# RH034_2.net
KiCad netlist of a schematic drawn in EAGLE
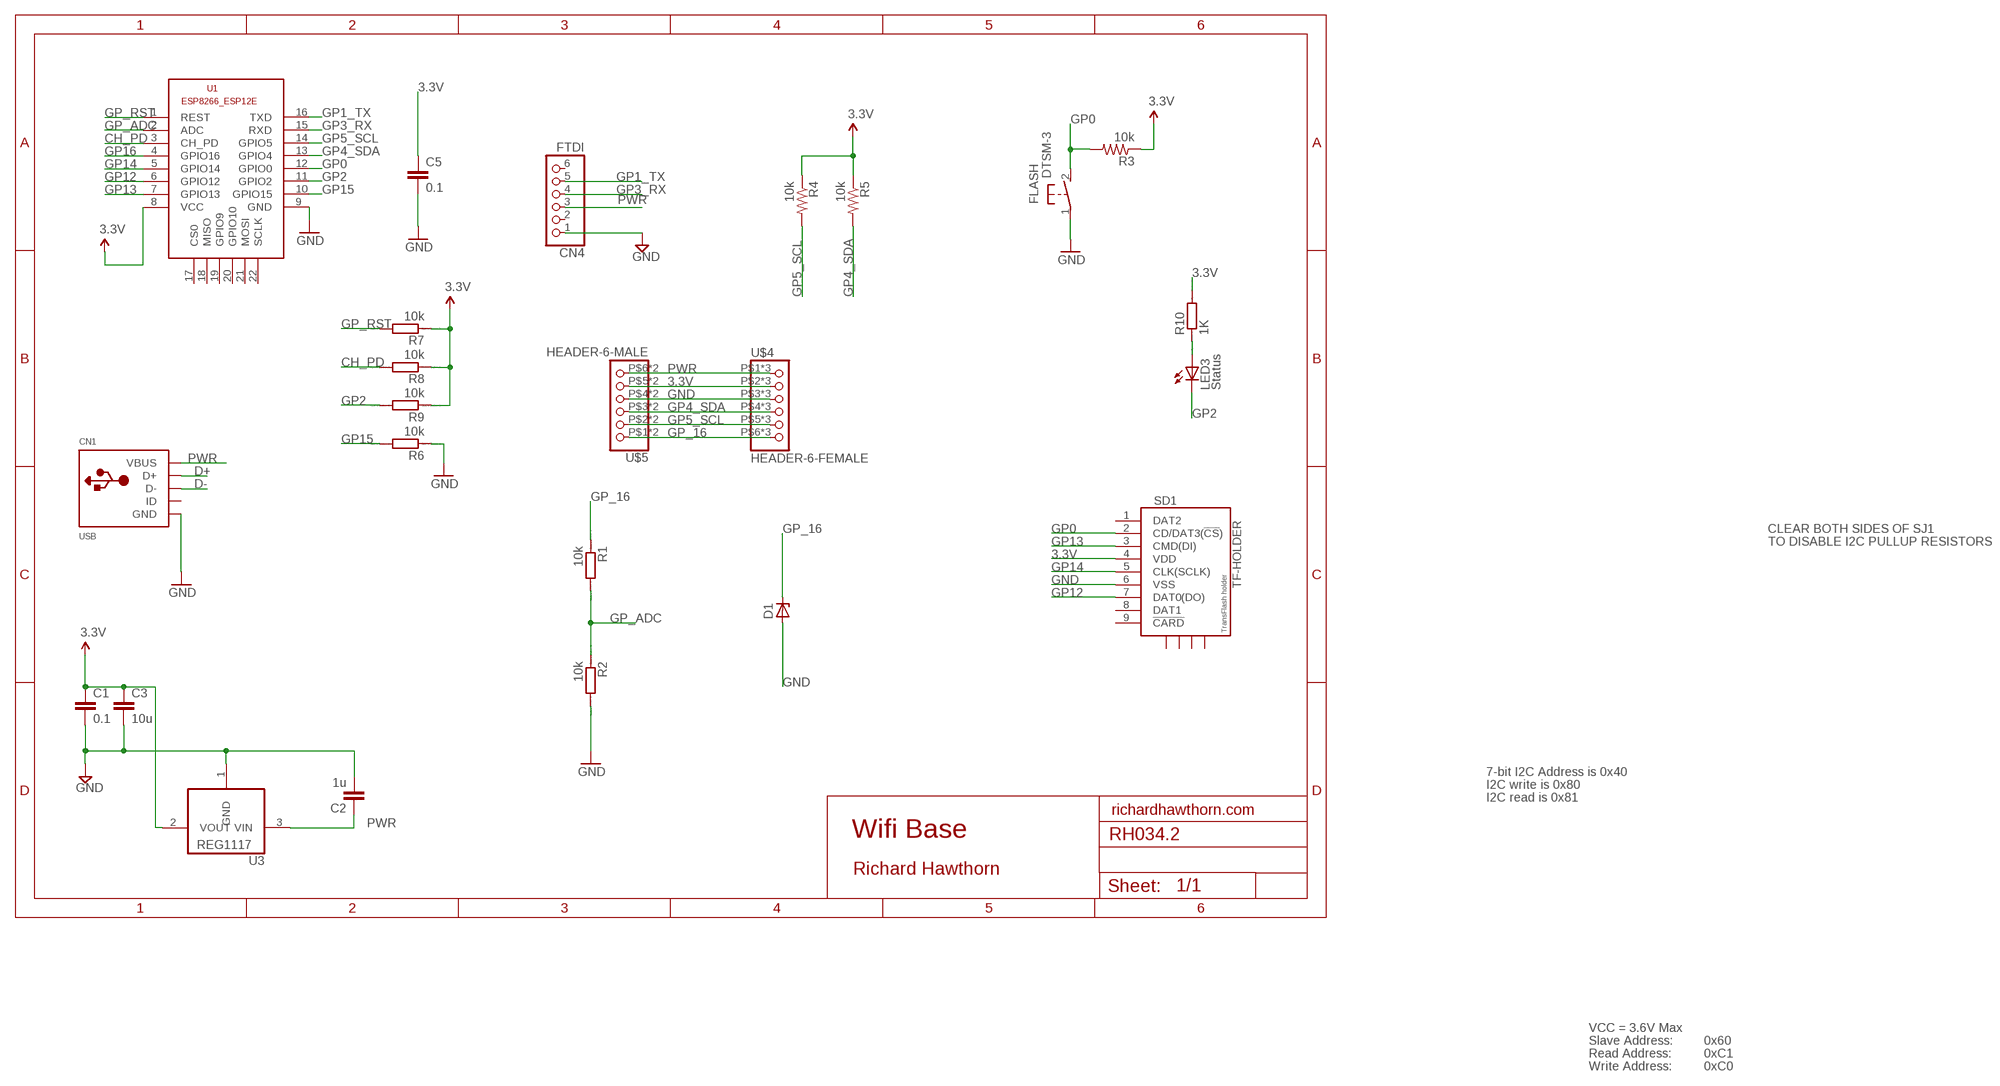
[diagram p0: schematic, sheet 1]

(export (version "E")
  (design (tool "Eeschema 10.0.6"))
  (components
    (comp (ref "C1")
      (value "0.1")
      (footprint "eagle-import:0603-CAP")
      (libsource (lib "eagle-import") (part "CAP0603-CAP"))
    )
    (comp (ref "C2")
      (value "1u")
      (footprint "eagle-import:0603-CAP")
      (libsource (lib "eagle-import") (part "CAP0603-CAP"))
    )
    (comp (ref "C3")
      (value "10u")
      (footprint "eagle-import:0805-CAP")
      (libsource (lib "eagle-import") (part "CAP0805-CAP"))
    )
    (comp (ref "C5")
      (value "0.1")
      (footprint "eagle-import:0603-CAP")
      (libsource (lib "eagle-import") (part "CAP0603-CAP"))
    )
    (comp (ref "CN1")
      (value "USB")
      (footprint "eagle-import:USB-MINIB")
      (libsource (lib "eagle-import") (part "USBMINIB"))
    )
    (comp (ref "CN4")
      (value "FTDI")
      (footprint "eagle-import:1X06")
      (libsource (lib "eagle-import") (part "PINHD-1X6"))
    )
    (comp (ref "D1")
      (value "ZENER-DIODESOT23")
      (footprint "eagle-import:SOT23")
      (libsource (lib "eagle-import") (part "ZENER-DIODESOT23"))
    )
    (comp (ref "FLASH")
      (value "DTSM-3")
      (footprint "eagle-import:DTSM-3")
      (libsource (lib "eagle-import") (part "DTSM-3"))
    )
    (comp (ref "LED3")
      (value "Status")
      (footprint "eagle-import:CHIPLED_0805")
      (libsource (lib "eagle-import") (part "LEDCHIPLED_0805"))
    )
    (comp (ref "R1")
      (value "10k")
      (footprint "eagle-import:R0603")
      (libsource (lib "eagle-import") (part "R-EU_R0603"))
    )
    (comp (ref "R2")
      (value "10k")
      (footprint "eagle-import:R0603")
      (libsource (lib "eagle-import") (part "R-EU_R0603"))
    )
    (comp (ref "R3")
      (value "10k")
      (footprint "eagle-import:0805")
      (libsource (lib "eagle-import") (part "RESISTOR0805-RES"))
    )
    (comp (ref "R4")
      (value "10k")
      (footprint "eagle-import:0805")
      (libsource (lib "eagle-import") (part "RESISTOR0805-RES"))
    )
    (comp (ref "R5")
      (value "10k")
      (footprint "eagle-import:0805")
      (libsource (lib "eagle-import") (part "RESISTOR0805-RES"))
    )
    (comp (ref "R6")
      (value "10k")
      (footprint "eagle-import:R0603")
      (libsource (lib "eagle-import") (part "R-EU_R0603"))
    )
    (comp (ref "R7")
      (value "10k")
      (footprint "eagle-import:R0603")
      (libsource (lib "eagle-import") (part "R-EU_R0603"))
    )
    (comp (ref "R8")
      (value "10k")
      (footprint "eagle-import:R0603")
      (libsource (lib "eagle-import") (part "R-EU_R0603"))
    )
    (comp (ref "R9")
      (value "10k")
      (footprint "eagle-import:R0603")
      (libsource (lib "eagle-import") (part "R-EU_R0603"))
    )
    (comp (ref "R10")
      (value "1K")
      (footprint "eagle-import:R0603")
      (libsource (lib "eagle-import") (part "R-EU_R0603"))
    )
    (comp (ref "SD1")
      (value "TF-HOLDER")
      (footprint "eagle-import:TF-PULL")
      (libsource (lib "eagle-import") (part "TF-HOLDER"))
    )
    (comp (ref "U$4")
      (value "HEADER-6-FEMALE")
      (footprint "eagle-import:2MMHEADER6")
      (libsource (lib "eagle-import") (part "HEADER-6-FEMALE"))
    )
    (comp (ref "U$5")
      (value "HEADER-6-MALE")
      (footprint "eagle-import:2MMHEADERPIN6")
      (libsource (lib "eagle-import") (part "HEADER-6-MALE"))
    )
    (comp (ref "U1")
      (value "ESP8266-12EESP8266-ESP12E")
      (footprint "eagle-import:ESP8266-ESP12E")
      (libsource (lib "eagle-import") (part "ESP8266-12EESP8266-ESP12E"))
    )
    (comp (ref "U3")
      (value "REG1117")
      (footprint "eagle-import:SOT223")
      (libsource (lib "eagle-import") (part "REG1117"))
    )
  )
  (nets
    (net (code "1") (name "/CH_PD") (class "Default")
      (node (ref "R8") (pin "2") (pinfunction "2_2") (pintype "passive"))
      (node (ref "U1") (pin "3") (pinfunction "CH_PD_3") (pintype "bidirectional"))
    )
    (net (code "2") (name "/D+") (class "Default")
      (node (ref "CN1") (pin "D+") (pinfunction "D+_D+") (pintype "bidirectional"))
    )
    (net (code "3") (name "/D-") (class "Default")
      (node (ref "CN1") (pin "D-") (pinfunction "D-_D-") (pintype "bidirectional"))
    )
    (net (code "4") (name "/GP0") (class "Default")
      (node (ref "FLASH") (pin "2") (pinfunction "2_2") (pintype "passive"))
      (node (ref "R3") (pin "2") (pinfunction "2_2") (pintype "passive"))
      (node (ref "SD1") (pin "2") (pinfunction "CD/DAT3(~{CS})_2") (pintype "bidirectional"))
      (node (ref "U1") (pin "12") (pinfunction "GPIO0_12") (pintype "bidirectional"))
    )
    (net (code "5") (name "/GP1_TX") (class "Default")
      (node (ref "CN4") (pin "5") (pinfunction "5_5") (pintype "passive"))
      (node (ref "U1") (pin "16") (pinfunction "TXD_16") (pintype "bidirectional"))
    )
    (net (code "6") (name "/GP2") (class "Default")
      (node (ref "LED3") (pin "C") (pinfunction "C_C") (pintype "passive"))
      (node (ref "R9") (pin "2") (pinfunction "2_2") (pintype "passive"))
      (node (ref "U1") (pin "11") (pinfunction "GPIO2_11") (pintype "bidirectional"))
    )
    (net (code "7") (name "/GP3_RX") (class "Default")
      (node (ref "CN4") (pin "4") (pinfunction "4_4") (pintype "passive"))
      (node (ref "U1") (pin "15") (pinfunction "RXD_15") (pintype "bidirectional"))
    )
    (net (code "8") (name "/GP4_SDA") (class "Default")
      (node (ref "R5") (pin "2") (pinfunction "2_2") (pintype "passive"))
      (node (ref "U$4") (pin "P$12") (pinfunction "4_P$12") (pintype "passive"))
      (node (ref "U$4") (pin "P$20") (pinfunction "4_P$20") (pintype "passive"))
      (node (ref "U$4") (pin "P$4") (pinfunction "4_P$4") (pintype "passive"))
      (node (ref "U$5") (pin "P$11") (pinfunction "3_P$11") (pintype "passive"))
      (node (ref "U$5") (pin "P$3") (pinfunction "3_P$3") (pintype "passive"))
      (node (ref "U1") (pin "13") (pinfunction "GPIO4_13") (pintype "bidirectional"))
    )
    (net (code "9") (name "/GP5_SCL") (class "Default")
      (node (ref "R4") (pin "2") (pinfunction "2_2") (pintype "passive"))
      (node (ref "U$4") (pin "P$13") (pinfunction "5_P$13") (pintype "passive"))
      (node (ref "U$4") (pin "P$21") (pinfunction "5_P$21") (pintype "passive"))
      (node (ref "U$4") (pin "P$5") (pinfunction "5_P$5") (pintype "passive"))
      (node (ref "U$5") (pin "P$10") (pinfunction "2_P$10") (pintype "passive"))
      (node (ref "U$5") (pin "P$2") (pinfunction "2_P$2") (pintype "passive"))
      (node (ref "U1") (pin "14") (pinfunction "GPIO5_14") (pintype "bidirectional"))
    )
    (net (code "10") (name "/GP12") (class "Default")
      (node (ref "SD1") (pin "7") (pinfunction "DAT0(DO)_7") (pintype "bidirectional"))
      (node (ref "U1") (pin "6") (pinfunction "GPIO12_6") (pintype "bidirectional"))
    )
    (net (code "11") (name "/GP13") (class "Default")
      (node (ref "SD1") (pin "3") (pinfunction "CMD(DI)_3") (pintype "bidirectional"))
      (node (ref "U1") (pin "7") (pinfunction "GPIO13_7") (pintype "bidirectional"))
    )
    (net (code "12") (name "/GP14") (class "Default")
      (node (ref "SD1") (pin "5") (pinfunction "CLK(SCLK)_5") (pintype "input"))
      (node (ref "U1") (pin "5") (pinfunction "GPIO14_5") (pintype "bidirectional"))
    )
    (net (code "13") (name "/GP15") (class "Default")
      (node (ref "R6") (pin "2") (pinfunction "2_2") (pintype "passive"))
      (node (ref "U1") (pin "10") (pinfunction "GPIO15_10") (pintype "bidirectional"))
    )
    (net (code "14") (name "/GP16") (class "Default")
      (node (ref "U1") (pin "4") (pinfunction "GPIO16_4") (pintype "bidirectional"))
    )
    (net (code "15") (name "/GP_16") (class "Default")
      (node (ref "D1") (pin "3") (pinfunction "C_3") (pintype "passive"))
      (node (ref "R1") (pin "1") (pinfunction "1_1") (pintype "passive"))
      (node (ref "U$4") (pin "P$14") (pinfunction "6_P$14") (pintype "passive"))
      (node (ref "U$4") (pin "P$22") (pinfunction "6_P$22") (pintype "passive"))
      (node (ref "U$4") (pin "P$6") (pinfunction "6_P$6") (pintype "passive"))
      (node (ref "U$5") (pin "P$1") (pinfunction "1_P$1") (pintype "passive"))
      (node (ref "U$5") (pin "P$9") (pinfunction "1_P$9") (pintype "passive"))
    )
    (net (code "16") (name "/GP_ADC") (class "Default")
      (node (ref "R1") (pin "2") (pinfunction "2_2") (pintype "passive"))
      (node (ref "R2") (pin "1") (pinfunction "1_1") (pintype "passive"))
      (node (ref "U1") (pin "2") (pinfunction "ADC_2") (pintype "bidirectional"))
    )
    (net (code "17") (name "/GP_RST") (class "Default")
      (node (ref "R7") (pin "2") (pinfunction "2_2") (pintype "passive"))
      (node (ref "U1") (pin "1") (pinfunction "REST_1") (pintype "bidirectional"))
    )
    (net (code "18") (name "/PWR") (class "Default")
      (node (ref "C2") (pin "1") (pinfunction "1_1") (pintype "passive"))
      (node (ref "CN1") (pin "VBUS") (pinfunction "VBUS_VBUS") (pintype "power_in"))
      (node (ref "CN4") (pin "3") (pinfunction "3_3") (pintype "passive"))
      (node (ref "U$4") (pin "P$1") (pinfunction "1_P$1") (pintype "passive"))
      (node (ref "U$4") (pin "P$17") (pinfunction "1_P$17") (pintype "passive"))
      (node (ref "U$4") (pin "P$9") (pinfunction "1_P$9") (pintype "passive"))
      (node (ref "U$5") (pin "P$14") (pinfunction "6_P$14") (pintype "passive"))
      (node (ref "U$5") (pin "P$6") (pinfunction "6_P$6") (pintype "passive"))
      (node (ref "U3") (pin "3") (pinfunction "VIN_3") (pintype "input"))
    )
    (net (code "19") (name "3.3V") (class "Default")
      (node (ref "C1") (pin "1") (pinfunction "1_1") (pintype "passive"))
      (node (ref "C3") (pin "1") (pinfunction "1_1") (pintype "passive"))
      (node (ref "C5") (pin "1") (pinfunction "1_1") (pintype "passive"))
      (node (ref "R10") (pin "2") (pinfunction "2_2") (pintype "passive"))
      (node (ref "R3") (pin "1") (pinfunction "1_1") (pintype "passive"))
      (node (ref "R4") (pin "1") (pinfunction "1_1") (pintype "passive"))
      (node (ref "R5") (pin "1") (pinfunction "1_1") (pintype "passive"))
      (node (ref "R7") (pin "1") (pinfunction "1_1") (pintype "passive"))
      (node (ref "R8") (pin "1") (pinfunction "1_1") (pintype "passive"))
      (node (ref "R9") (pin "1") (pinfunction "1_1") (pintype "passive"))
      (node (ref "SD1") (pin "4") (pinfunction "VDD_4") (pintype "power_in"))
      (node (ref "U$4") (pin "P$10") (pinfunction "2_P$10") (pintype "passive"))
      (node (ref "U$4") (pin "P$18") (pinfunction "2_P$18") (pintype "passive"))
      (node (ref "U$4") (pin "P$2") (pinfunction "2_P$2") (pintype "passive"))
      (node (ref "U$5") (pin "P$13") (pinfunction "5_P$13") (pintype "passive"))
      (node (ref "U$5") (pin "P$5") (pinfunction "5_P$5") (pintype "passive"))
      (node (ref "U1") (pin "8") (pinfunction "VCC_8") (pintype "bidirectional"))
      (node (ref "U3") (pin "2") (pinfunction "VOUT_2") (pintype "output"))
    )
    (net (code "20") (name "GND") (class "Default")
      (node (ref "C1") (pin "2") (pinfunction "2_2") (pintype "passive"))
      (node (ref "C2") (pin "2") (pinfunction "2_2") (pintype "passive"))
      (node (ref "C3") (pin "2") (pinfunction "2_2") (pintype "passive"))
      (node (ref "C5") (pin "2") (pinfunction "2_2") (pintype "passive"))
      (node (ref "CN1") (pin "GND") (pinfunction "GND_GND") (pintype "power_in"))
      (node (ref "CN4") (pin "1") (pinfunction "1_1") (pintype "passive"))
      (node (ref "D1") (pin "1") (pinfunction "A_1") (pintype "passive"))
      (node (ref "FLASH") (pin "1") (pinfunction "1_1") (pintype "passive"))
      (node (ref "R2") (pin "2") (pinfunction "2_2") (pintype "passive"))
      (node (ref "R6") (pin "1") (pinfunction "1_1") (pintype "passive"))
      (node (ref "SD1") (pin "6") (pinfunction "VSS_6") (pintype "power_in"))
      (node (ref "U$4") (pin "P$11") (pinfunction "3_P$11") (pintype "passive"))
      (node (ref "U$4") (pin "P$19") (pinfunction "3_P$19") (pintype "passive"))
      (node (ref "U$4") (pin "P$3") (pinfunction "3_P$3") (pintype "passive"))
      (node (ref "U$5") (pin "P$12") (pinfunction "4_P$12") (pintype "passive"))
      (node (ref "U$5") (pin "P$4") (pinfunction "4_P$4") (pintype "passive"))
      (node (ref "U1") (pin "9") (pinfunction "GND_9") (pintype "bidirectional"))
      (node (ref "U3") (pin "1") (pinfunction "GND_1") (pintype "power_in"))
    )
    (net (code "21") (name "Net-(LED3-PadA)") (class "Default")
      (node (ref "LED3") (pin "A") (pinfunction "A_A") (pintype "passive"))
      (node (ref "R10") (pin "1") (pinfunction "1_1") (pintype "passive"))
    )
    (net (code "22") (name "unconnected-(CN1-PadID)") (class "Default")
      (node (ref "CN1") (pin "ID") (pinfunction "ID_ID") (pintype "bidirectional"))
    )
    (net (code "23") (name "unconnected-(CN4-Pad2)") (class "Default")
      (node (ref "CN4") (pin "2") (pinfunction "2_2") (pintype "passive"))
    )
    (net (code "24") (name "unconnected-(CN4-Pad6)") (class "Default")
      (node (ref "CN4") (pin "6") (pinfunction "6_6") (pintype "passive"))
    )
    (net (code "25") (name "unconnected-(SD1-DAT1-Pad8)") (class "Default")
      (node (ref "SD1") (pin "8") (pinfunction "DAT1_8") (pintype "bidirectional"))
    )
    (net (code "26") (name "unconnected-(SD1-DAT2-Pad1)") (class "Default")
      (node (ref "SD1") (pin "1") (pinfunction "DAT2_1") (pintype "bidirectional"))
    )
    (net (code "27") (name "unconnected-(SD1-PadS1)") (class "Default")
      (node (ref "SD1") (pin "S1") (pinfunction "S1_S1") (pintype "passive"))
    )
    (net (code "28") (name "unconnected-(SD1-PadS2)") (class "Default")
      (node (ref "SD1") (pin "S2") (pinfunction "S2_S2") (pintype "passive"))
    )
    (net (code "29") (name "unconnected-(SD1-PadS3)") (class "Default")
      (node (ref "SD1") (pin "S3") (pinfunction "S3_S3") (pintype "passive"))
    )
    (net (code "30") (name "unconnected-(SD1-PadS4)") (class "Default")
      (node (ref "SD1") (pin "S4") (pinfunction "S4_S4") (pintype "passive"))
    )
    (net (code "31") (name "unconnected-(SD1-~{CARD}-Pad9)") (class "Default")
      (node (ref "SD1") (pin "9") (pinfunction "~{CARD}_9") (pintype "passive"))
    )
    (net (code "32") (name "unconnected-(U1-CS0-Pad17)") (class "Default")
      (node (ref "U1") (pin "17") (pinfunction "CS0_17") (pintype "bidirectional"))
    )
    (net (code "33") (name "unconnected-(U1-GPIO9-Pad19)") (class "Default")
      (node (ref "U1") (pin "19") (pinfunction "GPIO9_19") (pintype "bidirectional"))
    )
    (net (code "34") (name "unconnected-(U1-GPIO10-Pad20)") (class "Default")
      (node (ref "U1") (pin "20") (pinfunction "GPIO10_20") (pintype "bidirectional"))
    )
    (net (code "35") (name "unconnected-(U1-MISO-Pad18)") (class "Default")
      (node (ref "U1") (pin "18") (pinfunction "MISO_18") (pintype "bidirectional"))
    )
    (net (code "36") (name "unconnected-(U1-MOSI-Pad21)") (class "Default")
      (node (ref "U1") (pin "21") (pinfunction "MOSI_21") (pintype "bidirectional"))
    )
    (net (code "37") (name "unconnected-(U1-SCLK-Pad22)") (class "Default")
      (node (ref "U1") (pin "22") (pinfunction "SCLK_22") (pintype "bidirectional"))
    )
  )
)
